# PixelWing_rev0_1.net
KiCad netlist of a schematic drawn in EAGLE
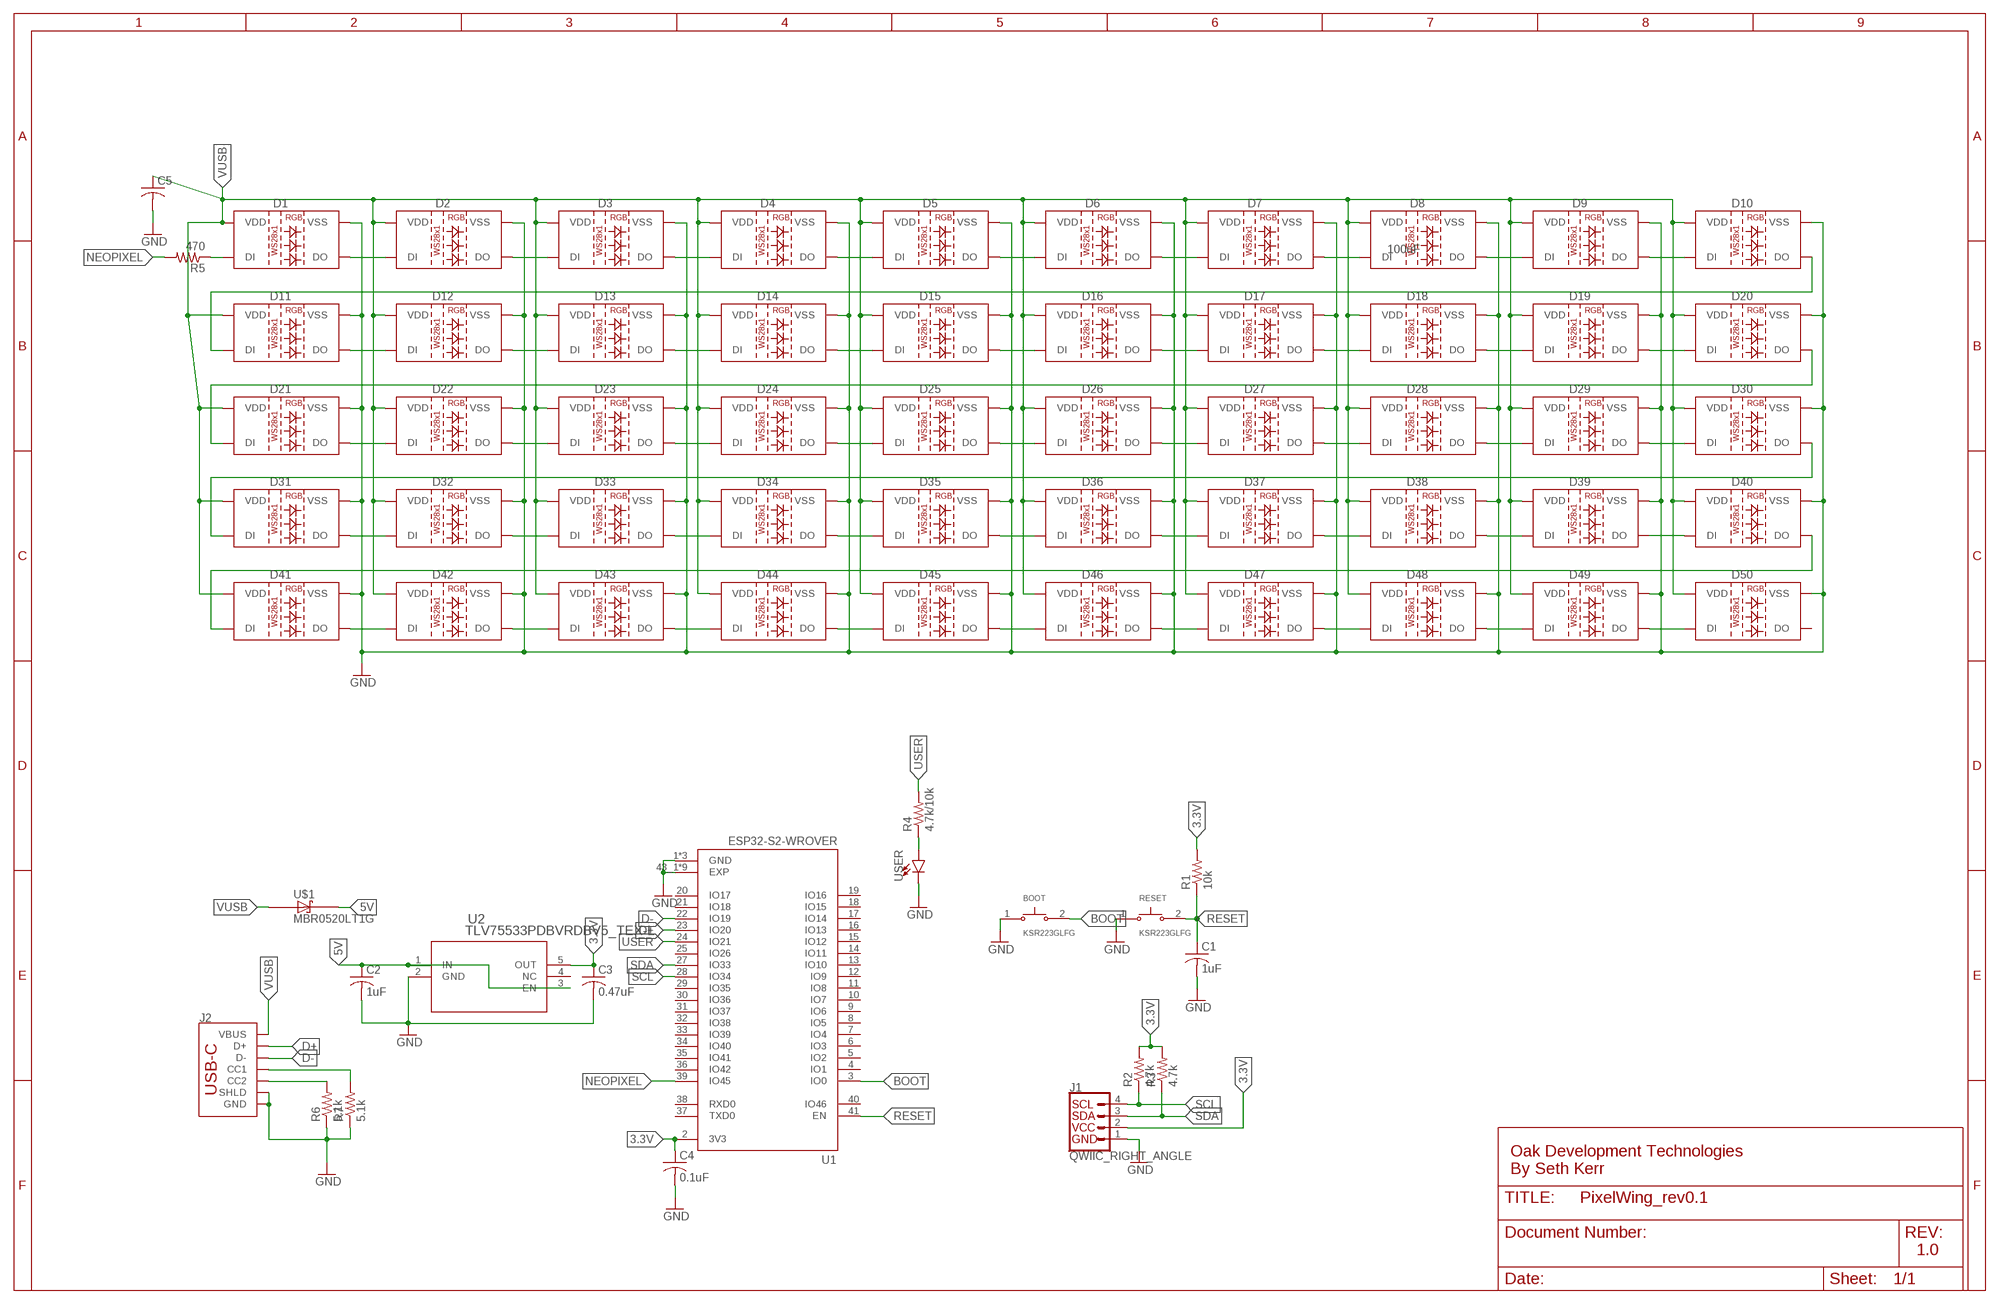
[diagram p0: schematic, sheet 1]

(export (version "E")
  (design (tool "Eeschema 10.0.6"))
  (components
    (comp (ref "BOOT")
      (value "KSR223GLFG")
      (footprint "eagle-import:SW_KSR223GLFG")
      (fields (field (name "MF") "C&K"))
      (libsource (lib "eagle-import") (part "KSR223GLFG"))
    )
    (comp (ref "C1")
      (value "1uF")
      (footprint "eagle-import:C0603")
      (libsource (lib "eagle-import") (part "C-USC0603"))
    )
    (comp (ref "C2")
      (value "1uF")
      (footprint "eagle-import:C0603")
      (libsource (lib "eagle-import") (part "C-USC0603"))
    )
    (comp (ref "C3")
      (value "0.47uF")
      (footprint "eagle-import:C0603")
      (libsource (lib "eagle-import") (part "C-USC0603"))
    )
    (comp (ref "C4")
      (value "0.1uF")
      (footprint "eagle-import:C0603")
      (libsource (lib "eagle-import") (part "C-USC0603"))
    )
    (comp (ref "C5")
      (value "100uF")
      (footprint "eagle-import:C1206")
      (libsource (lib "eagle-import") (part "C-USC1206"))
    )
    (comp (ref "D1")
      (value "WS2812BWS2812B-3535")
      (footprint "eagle-import:WS2812-3535")
      (libsource (lib "eagle-import") (part "WS2812BWS2812B-3535"))
    )
    (comp (ref "D2")
      (value "WS2812BWS2812B-3535")
      (footprint "eagle-import:WS2812-3535")
      (libsource (lib "eagle-import") (part "WS2812BWS2812B-3535"))
    )
    (comp (ref "D3")
      (value "WS2812BWS2812B-3535")
      (footprint "eagle-import:WS2812-3535")
      (libsource (lib "eagle-import") (part "WS2812BWS2812B-3535"))
    )
    (comp (ref "D4")
      (value "WS2812BWS2812B-3535")
      (footprint "eagle-import:WS2812-3535")
      (libsource (lib "eagle-import") (part "WS2812BWS2812B-3535"))
    )
    (comp (ref "D5")
      (value "WS2812BWS2812B-3535")
      (footprint "eagle-import:WS2812-3535")
      (libsource (lib "eagle-import") (part "WS2812BWS2812B-3535"))
    )
    (comp (ref "D6")
      (value "WS2812BWS2812B-3535")
      (footprint "eagle-import:WS2812-3535")
      (libsource (lib "eagle-import") (part "WS2812BWS2812B-3535"))
    )
    (comp (ref "D7")
      (value "WS2812BWS2812B-3535")
      (footprint "eagle-import:WS2812-3535")
      (libsource (lib "eagle-import") (part "WS2812BWS2812B-3535"))
    )
    (comp (ref "D8")
      (value "WS2812BWS2812B-3535")
      (footprint "eagle-import:WS2812-3535")
      (libsource (lib "eagle-import") (part "WS2812BWS2812B-3535"))
    )
    (comp (ref "D9")
      (value "WS2812BWS2812B-3535")
      (footprint "eagle-import:WS2812-3535")
      (libsource (lib "eagle-import") (part "WS2812BWS2812B-3535"))
    )
    (comp (ref "D10")
      (value "WS2812BWS2812B-3535")
      (footprint "eagle-import:WS2812-3535")
      (libsource (lib "eagle-import") (part "WS2812BWS2812B-3535"))
    )
    (comp (ref "D11")
      (value "WS2812BWS2812B-3535")
      (footprint "eagle-import:WS2812-3535")
      (libsource (lib "eagle-import") (part "WS2812BWS2812B-3535"))
    )
    (comp (ref "D12")
      (value "WS2812BWS2812B-3535")
      (footprint "eagle-import:WS2812-3535")
      (libsource (lib "eagle-import") (part "WS2812BWS2812B-3535"))
    )
    (comp (ref "D13")
      (value "WS2812BWS2812B-3535")
      (footprint "eagle-import:WS2812-3535")
      (libsource (lib "eagle-import") (part "WS2812BWS2812B-3535"))
    )
    (comp (ref "D14")
      (value "WS2812BWS2812B-3535")
      (footprint "eagle-import:WS2812-3535")
      (libsource (lib "eagle-import") (part "WS2812BWS2812B-3535"))
    )
    (comp (ref "D15")
      (value "WS2812BWS2812B-3535")
      (footprint "eagle-import:WS2812-3535")
      (libsource (lib "eagle-import") (part "WS2812BWS2812B-3535"))
    )
    (comp (ref "D16")
      (value "WS2812BWS2812B-3535")
      (footprint "eagle-import:WS2812-3535")
      (libsource (lib "eagle-import") (part "WS2812BWS2812B-3535"))
    )
    (comp (ref "D17")
      (value "WS2812BWS2812B-3535")
      (footprint "eagle-import:WS2812-3535")
      (libsource (lib "eagle-import") (part "WS2812BWS2812B-3535"))
    )
    (comp (ref "D18")
      (value "WS2812BWS2812B-3535")
      (footprint "eagle-import:WS2812-3535")
      (libsource (lib "eagle-import") (part "WS2812BWS2812B-3535"))
    )
    (comp (ref "D19")
      (value "WS2812BWS2812B-3535")
      (footprint "eagle-import:WS2812-3535")
      (libsource (lib "eagle-import") (part "WS2812BWS2812B-3535"))
    )
    (comp (ref "D20")
      (value "WS2812BWS2812B-3535")
      (footprint "eagle-import:WS2812-3535")
      (libsource (lib "eagle-import") (part "WS2812BWS2812B-3535"))
    )
    (comp (ref "D21")
      (value "WS2812BWS2812B-3535")
      (footprint "eagle-import:WS2812-3535")
      (libsource (lib "eagle-import") (part "WS2812BWS2812B-3535"))
    )
    (comp (ref "D22")
      (value "WS2812BWS2812B-3535")
      (footprint "eagle-import:WS2812-3535")
      (libsource (lib "eagle-import") (part "WS2812BWS2812B-3535"))
    )
    (comp (ref "D23")
      (value "WS2812BWS2812B-3535")
      (footprint "eagle-import:WS2812-3535")
      (libsource (lib "eagle-import") (part "WS2812BWS2812B-3535"))
    )
    (comp (ref "D24")
      (value "WS2812BWS2812B-3535")
      (footprint "eagle-import:WS2812-3535")
      (libsource (lib "eagle-import") (part "WS2812BWS2812B-3535"))
    )
    (comp (ref "D25")
      (value "WS2812BWS2812B-3535")
      (footprint "eagle-import:WS2812-3535")
      (libsource (lib "eagle-import") (part "WS2812BWS2812B-3535"))
    )
    (comp (ref "D26")
      (value "WS2812BWS2812B-3535")
      (footprint "eagle-import:WS2812-3535")
      (libsource (lib "eagle-import") (part "WS2812BWS2812B-3535"))
    )
    (comp (ref "D27")
      (value "WS2812BWS2812B-3535")
      (footprint "eagle-import:WS2812-3535")
      (libsource (lib "eagle-import") (part "WS2812BWS2812B-3535"))
    )
    (comp (ref "D28")
      (value "WS2812BWS2812B-3535")
      (footprint "eagle-import:WS2812-3535")
      (libsource (lib "eagle-import") (part "WS2812BWS2812B-3535"))
    )
    (comp (ref "D29")
      (value "WS2812BWS2812B-3535")
      (footprint "eagle-import:WS2812-3535")
      (libsource (lib "eagle-import") (part "WS2812BWS2812B-3535"))
    )
    (comp (ref "D30")
      (value "WS2812BWS2812B-3535")
      (footprint "eagle-import:WS2812-3535")
      (libsource (lib "eagle-import") (part "WS2812BWS2812B-3535"))
    )
    (comp (ref "D31")
      (value "WS2812BWS2812B-3535")
      (footprint "eagle-import:WS2812-3535")
      (libsource (lib "eagle-import") (part "WS2812BWS2812B-3535"))
    )
    (comp (ref "D32")
      (value "WS2812BWS2812B-3535")
      (footprint "eagle-import:WS2812-3535")
      (libsource (lib "eagle-import") (part "WS2812BWS2812B-3535"))
    )
    (comp (ref "D33")
      (value "WS2812BWS2812B-3535")
      (footprint "eagle-import:WS2812-3535")
      (libsource (lib "eagle-import") (part "WS2812BWS2812B-3535"))
    )
    (comp (ref "D34")
      (value "WS2812BWS2812B-3535")
      (footprint "eagle-import:WS2812-3535")
      (libsource (lib "eagle-import") (part "WS2812BWS2812B-3535"))
    )
    (comp (ref "D35")
      (value "WS2812BWS2812B-3535")
      (footprint "eagle-import:WS2812-3535")
      (libsource (lib "eagle-import") (part "WS2812BWS2812B-3535"))
    )
    (comp (ref "D36")
      (value "WS2812BWS2812B-3535")
      (footprint "eagle-import:WS2812-3535")
      (libsource (lib "eagle-import") (part "WS2812BWS2812B-3535"))
    )
    (comp (ref "D37")
      (value "WS2812BWS2812B-3535")
      (footprint "eagle-import:WS2812-3535")
      (libsource (lib "eagle-import") (part "WS2812BWS2812B-3535"))
    )
    (comp (ref "D38")
      (value "WS2812BWS2812B-3535")
      (footprint "eagle-import:WS2812-3535")
      (libsource (lib "eagle-import") (part "WS2812BWS2812B-3535"))
    )
    (comp (ref "D39")
      (value "WS2812BWS2812B-3535")
      (footprint "eagle-import:WS2812-3535")
      (libsource (lib "eagle-import") (part "WS2812BWS2812B-3535"))
    )
    (comp (ref "D40")
      (value "WS2812BWS2812B-3535")
      (footprint "eagle-import:WS2812-3535")
      (libsource (lib "eagle-import") (part "WS2812BWS2812B-3535"))
    )
    (comp (ref "D41")
      (value "WS2812BWS2812B-3535")
      (footprint "eagle-import:WS2812-3535")
      (libsource (lib "eagle-import") (part "WS2812BWS2812B-3535"))
    )
    (comp (ref "D42")
      (value "WS2812BWS2812B-3535")
      (footprint "eagle-import:WS2812-3535")
      (libsource (lib "eagle-import") (part "WS2812BWS2812B-3535"))
    )
    (comp (ref "D43")
      (value "WS2812BWS2812B-3535")
      (footprint "eagle-import:WS2812-3535")
      (libsource (lib "eagle-import") (part "WS2812BWS2812B-3535"))
    )
    (comp (ref "D44")
      (value "WS2812BWS2812B-3535")
      (footprint "eagle-import:WS2812-3535")
      (libsource (lib "eagle-import") (part "WS2812BWS2812B-3535"))
    )
    (comp (ref "D45")
      (value "WS2812BWS2812B-3535")
      (footprint "eagle-import:WS2812-3535")
      (libsource (lib "eagle-import") (part "WS2812BWS2812B-3535"))
    )
    (comp (ref "D46")
      (value "WS2812BWS2812B-3535")
      (footprint "eagle-import:WS2812-3535")
      (libsource (lib "eagle-import") (part "WS2812BWS2812B-3535"))
    )
    (comp (ref "D47")
      (value "WS2812BWS2812B-3535")
      (footprint "eagle-import:WS2812-3535")
      (libsource (lib "eagle-import") (part "WS2812BWS2812B-3535"))
    )
    (comp (ref "D48")
      (value "WS2812BWS2812B-3535")
      (footprint "eagle-import:WS2812-3535")
      (libsource (lib "eagle-import") (part "WS2812BWS2812B-3535"))
    )
    (comp (ref "D49")
      (value "WS2812BWS2812B-3535")
      (footprint "eagle-import:WS2812-3535")
      (libsource (lib "eagle-import") (part "WS2812BWS2812B-3535"))
    )
    (comp (ref "D50")
      (value "WS2812BWS2812B-3535")
      (footprint "eagle-import:WS2812-3535")
      (libsource (lib "eagle-import") (part "WS2812BWS2812B-3535"))
    )
    (comp (ref "J1")
      (value "QWIIC_RIGHT_ANGLE")
      (footprint "eagle-import:JST04_1MM_RA")
      (libsource (lib "eagle-import") (part "QWIIC_CONNECTORJS-1MM"))
    )
    (comp (ref "J2")
      (value "USB_C_2-LAYER_PADS")
      (footprint "eagle-import:USB-C-16P-2LAYER-PADS")
      (libsource (lib "eagle-import") (part "USB_C_2-LAYER_PADS"))
    )
    (comp (ref "R1")
      (value "10k")
      (footprint "eagle-import:R0603")
      (libsource (lib "eagle-import") (part "R-US_R0603"))
    )
    (comp (ref "R2")
      (value "4.7k")
      (footprint "eagle-import:R0603")
      (libsource (lib "eagle-import") (part "R-US_R0603"))
    )
    (comp (ref "R3")
      (value "4.7k")
      (footprint "eagle-import:R0603")
      (libsource (lib "eagle-import") (part "R-US_R0603"))
    )
    (comp (ref "R4")
      (value "4.7k/10k")
      (footprint "eagle-import:R0603")
      (libsource (lib "eagle-import") (part "R-US_R0603"))
    )
    (comp (ref "R5")
      (value "470")
      (footprint "eagle-import:R0603")
      (libsource (lib "eagle-import") (part "R-US_R0603"))
    )
    (comp (ref "R6")
      (value "5.1k")
      (footprint "eagle-import:R0603")
      (libsource (lib "eagle-import") (part "R-US_R0603"))
    )
    (comp (ref "R7")
      (value "5.1k")
      (footprint "eagle-import:R0603")
      (libsource (lib "eagle-import") (part "R-US_R0603"))
    )
    (comp (ref "RESET")
      (value "KSR223GLFG")
      (footprint "eagle-import:SW_KSR223GLFG")
      (fields (field (name "MF") "C&K"))
      (libsource (lib "eagle-import") (part "KSR223GLFG"))
    )
    (comp (ref "U$1")
      (value "MBR0520LT1G")
      (footprint "eagle-import:SOD3716X117(SOD-123)")
      (fields (field (name "MF") "ON Semiconductor"))
      (libsource (lib "eagle-import") (part "MBR0520LT1G"))
    )
    (comp (ref "U1")
      (value "ESP32-S2-WROVER")
      (footprint "eagle-import:MODULE_ESP32-S2-WROVER")
      (fields (field (name "MF") "Espressif Systems"))
      (libsource (lib "eagle-import") (part "ESP32-S2-WROVER"))
    )
    (comp (ref "U2")
      (value "TLV75533PDBVRDBV5_TEX-L")
      (footprint "eagle-import:DBV5_TEX-L")
      (fields
        (field (name "MANUFACTURER_PART_NUMBER") "TLV75533PDBVR")
        (field (name "COPYRIGHT") "Copyright (C) 2018 Accelerated Designs. All rights reserved")
      )
      (libsource (lib "eagle-import") (part "TLV75533PDBVRDBV5_TEX-L"))
    )
    (comp (ref "USER")
      (value "LED0603")
      (footprint "eagle-import:LED-0603")
      (libsource (lib "eagle-import") (part "LED0603"))
    )
  )
  (nets
    (net (code "1") (name "3.3V") (class "Default")
      (node (ref "C3") (pin "1") (pinfunction "1_1") (pintype "passive"))
      (node (ref "C4") (pin "1") (pinfunction "1_1") (pintype "passive"))
      (node (ref "J1") (pin "2") (pinfunction "2_2") (pintype "power_in"))
      (node (ref "R1") (pin "2") (pinfunction "2_2") (pintype "passive"))
      (node (ref "R2") (pin "2") (pinfunction "2_2") (pintype "passive"))
      (node (ref "R3") (pin "2") (pinfunction "2_2") (pintype "passive"))
      (node (ref "U1") (pin "2") (pinfunction "3V3_2") (pintype "power_in"))
      (node (ref "U2") (pin "5") (pinfunction "OUT_5") (pintype "output"))
    )
    (net (code "2") (name "5V") (class "Default")
      (node (ref "C2") (pin "1") (pinfunction "1_1") (pintype "passive"))
      (node (ref "U$1") (pin "1") (pinfunction "C_1") (pintype "passive"))
      (node (ref "U2") (pin "1") (pinfunction "IN_1") (pintype "input"))
      (node (ref "U2") (pin "3") (pinfunction "EN_3") (pintype "input"))
    )
    (net (code "3") (name "BOOT") (class "Default")
      (node (ref "BOOT") (pin "2") (pinfunction "2_2") (pintype "passive"))
      (node (ref "U1") (pin "3") (pinfunction "IO0_3") (pintype "bidirectional"))
    )
    (net (code "4") (name "D+") (class "Default")
      (node (ref "J2") (pin "A6") (pinfunction "D+_A6") (pintype "bidirectional"))
      (node (ref "J2") (pin "B6") (pinfunction "D+_B6") (pintype "bidirectional"))
      (node (ref "U1") (pin "23") (pinfunction "IO20_23") (pintype "bidirectional"))
    )
    (net (code "5") (name "D-") (class "Default")
      (node (ref "J2") (pin "A7") (pinfunction "D-_A7") (pintype "bidirectional"))
      (node (ref "J2") (pin "B7") (pinfunction "D-_B7") (pintype "bidirectional"))
      (node (ref "U1") (pin "22") (pinfunction "IO19_22") (pintype "bidirectional"))
    )
    (net (code "6") (name "GND") (class "Default")
      (node (ref "BOOT") (pin "1") (pinfunction "1_1") (pintype "passive"))
      (node (ref "C1") (pin "2") (pinfunction "2_2") (pintype "passive"))
      (node (ref "C2") (pin "2") (pinfunction "2_2") (pintype "passive"))
      (node (ref "C3") (pin "2") (pinfunction "2_2") (pintype "passive"))
      (node (ref "C4") (pin "2") (pinfunction "2_2") (pintype "passive"))
      (node (ref "C5") (pin "2") (pinfunction "2_2") (pintype "passive"))
      (node (ref "D1") (pin "VSS") (pinfunction "VSS_VSS") (pintype "bidirectional"))
      (node (ref "D10") (pin "VSS") (pinfunction "VSS_VSS") (pintype "bidirectional"))
      (node (ref "D11") (pin "VSS") (pinfunction "VSS_VSS") (pintype "bidirectional"))
      (node (ref "D12") (pin "VSS") (pinfunction "VSS_VSS") (pintype "bidirectional"))
      (node (ref "D13") (pin "VSS") (pinfunction "VSS_VSS") (pintype "bidirectional"))
      (node (ref "D14") (pin "VSS") (pinfunction "VSS_VSS") (pintype "bidirectional"))
      (node (ref "D15") (pin "VSS") (pinfunction "VSS_VSS") (pintype "bidirectional"))
      (node (ref "D16") (pin "VSS") (pinfunction "VSS_VSS") (pintype "bidirectional"))
      (node (ref "D17") (pin "VSS") (pinfunction "VSS_VSS") (pintype "bidirectional"))
      (node (ref "D18") (pin "VSS") (pinfunction "VSS_VSS") (pintype "bidirectional"))
      (node (ref "D19") (pin "VSS") (pinfunction "VSS_VSS") (pintype "bidirectional"))
      (node (ref "D2") (pin "VSS") (pinfunction "VSS_VSS") (pintype "bidirectional"))
      (node (ref "D20") (pin "VSS") (pinfunction "VSS_VSS") (pintype "bidirectional"))
      (node (ref "D21") (pin "VSS") (pinfunction "VSS_VSS") (pintype "bidirectional"))
      (node (ref "D22") (pin "VSS") (pinfunction "VSS_VSS") (pintype "bidirectional"))
      (node (ref "D23") (pin "VSS") (pinfunction "VSS_VSS") (pintype "bidirectional"))
      (node (ref "D24") (pin "VSS") (pinfunction "VSS_VSS") (pintype "bidirectional"))
      (node (ref "D25") (pin "VSS") (pinfunction "VSS_VSS") (pintype "bidirectional"))
      (node (ref "D26") (pin "VSS") (pinfunction "VSS_VSS") (pintype "bidirectional"))
      (node (ref "D27") (pin "VSS") (pinfunction "VSS_VSS") (pintype "bidirectional"))
      (node (ref "D28") (pin "VSS") (pinfunction "VSS_VSS") (pintype "bidirectional"))
      (node (ref "D29") (pin "VSS") (pinfunction "VSS_VSS") (pintype "bidirectional"))
      (node (ref "D3") (pin "VSS") (pinfunction "VSS_VSS") (pintype "bidirectional"))
      (node (ref "D30") (pin "VSS") (pinfunction "VSS_VSS") (pintype "bidirectional"))
      (node (ref "D31") (pin "VSS") (pinfunction "VSS_VSS") (pintype "bidirectional"))
      (node (ref "D32") (pin "VSS") (pinfunction "VSS_VSS") (pintype "bidirectional"))
      (node (ref "D33") (pin "VSS") (pinfunction "VSS_VSS") (pintype "bidirectional"))
      (node (ref "D34") (pin "VSS") (pinfunction "VSS_VSS") (pintype "bidirectional"))
      (node (ref "D35") (pin "VSS") (pinfunction "VSS_VSS") (pintype "bidirectional"))
      (node (ref "D36") (pin "VSS") (pinfunction "VSS_VSS") (pintype "bidirectional"))
      (node (ref "D37") (pin "VSS") (pinfunction "VSS_VSS") (pintype "bidirectional"))
      (node (ref "D38") (pin "VSS") (pinfunction "VSS_VSS") (pintype "bidirectional"))
      (node (ref "D39") (pin "VSS") (pinfunction "VSS_VSS") (pintype "bidirectional"))
      (node (ref "D4") (pin "VSS") (pinfunction "VSS_VSS") (pintype "bidirectional"))
      (node (ref "D40") (pin "VSS") (pinfunction "VSS_VSS") (pintype "bidirectional"))
      (node (ref "D41") (pin "VSS") (pinfunction "VSS_VSS") (pintype "bidirectional"))
      (node (ref "D42") (pin "VSS") (pinfunction "VSS_VSS") (pintype "bidirectional"))
      (node (ref "D43") (pin "VSS") (pinfunction "VSS_VSS") (pintype "bidirectional"))
      (node (ref "D44") (pin "VSS") (pinfunction "VSS_VSS") (pintype "bidirectional"))
      (node (ref "D45") (pin "VSS") (pinfunction "VSS_VSS") (pintype "bidirectional"))
      (node (ref "D46") (pin "VSS") (pinfunction "VSS_VSS") (pintype "bidirectional"))
      (node (ref "D47") (pin "VSS") (pinfunction "VSS_VSS") (pintype "bidirectional"))
      (node (ref "D48") (pin "VSS") (pinfunction "VSS_VSS") (pintype "bidirectional"))
      (node (ref "D49") (pin "VSS") (pinfunction "VSS_VSS") (pintype "bidirectional"))
      (node (ref "D5") (pin "VSS") (pinfunction "VSS_VSS") (pintype "bidirectional"))
      (node (ref "D50") (pin "VSS") (pinfunction "VSS_VSS") (pintype "bidirectional"))
      (node (ref "D6") (pin "VSS") (pinfunction "VSS_VSS") (pintype "bidirectional"))
      (node (ref "D7") (pin "VSS") (pinfunction "VSS_VSS") (pintype "bidirectional"))
      (node (ref "D8") (pin "VSS") (pinfunction "VSS_VSS") (pintype "bidirectional"))
      (node (ref "D9") (pin "VSS") (pinfunction "VSS_VSS") (pintype "bidirectional"))
      (node (ref "J1") (pin "1") (pinfunction "1_1") (pintype "power_in"))
      (node (ref "J2") (pin "GND") (pinfunction "GND_GND") (pintype "bidirectional"))
      (node (ref "J2") (pin "GND2") (pinfunction "GND_GND2") (pintype "bidirectional"))
      (node (ref "J2") (pin "P$1") (pinfunction "SHLD_P$1") (pintype "bidirectional"))
      (node (ref "J2") (pin "P$2") (pinfunction "SHLD_P$2") (pintype "bidirectional"))
      (node (ref "J2") (pin "P$3") (pinfunction "SHLD_P$3") (pintype "bidirectional"))
      (node (ref "J2") (pin "P$4") (pinfunction "SHLD_P$4") (pintype "bidirectional"))
      (node (ref "J2") (pin "SHLD1") (pinfunction "SHLD_SHLD1") (pintype "bidirectional"))
      (node (ref "J2") (pin "SHLD2") (pinfunction "SHLD_SHLD2") (pintype "bidirectional"))
      (node (ref "J2") (pin "SHLD3") (pinfunction "SHLD_SHLD3") (pintype "bidirectional"))
      (node (ref "J2") (pin "SHLD4") (pinfunction "SHLD_SHLD4") (pintype "bidirectional"))
      (node (ref "R6") (pin "1") (pinfunction "1_1") (pintype "passive"))
      (node (ref "R7") (pin "1") (pinfunction "1_1") (pintype "passive"))
      (node (ref "RESET") (pin "1") (pinfunction "1_1") (pintype "passive"))
      (node (ref "U1") (pin "1") (pinfunction "GND_1") (pintype "power_in"))
      (node (ref "U1") (pin "26") (pinfunction "GND_26") (pintype "power_in"))
      (node (ref "U1") (pin "42") (pinfunction "GND_42") (pintype "power_in"))
      (node (ref "U1") (pin "43_1") (pinfunction "EXP_43_1") (pintype "power_in"))
      (node (ref "U1") (pin "43_2") (pinfunction "EXP_43_2") (pintype "power_in"))
      (node (ref "U1") (pin "43_3") (pinfunction "EXP_43_3") (pintype "power_in"))
      (node (ref "U1") (pin "43_4") (pinfunction "EXP_43_4") (pintype "power_in"))
      (node (ref "U1") (pin "43_5") (pinfunction "EXP_43_5") (pintype "power_in"))
      (node (ref "U1") (pin "43_6") (pinfunction "EXP_43_6") (pintype "power_in"))
      (node (ref "U1") (pin "43_7") (pinfunction "EXP_43_7") (pintype "power_in"))
      (node (ref "U1") (pin "43_8") (pinfunction "EXP_43_8") (pintype "power_in"))
      (node (ref "U1") (pin "43_9") (pinfunction "EXP_43_9") (pintype "power_in"))
      (node (ref "U2") (pin "2") (pinfunction "GND_2") (pintype "power_in"))
      (node (ref "USER") (pin "C") (pinfunction "C_C") (pintype "passive"))
    )
    (net (code "7") (name "NEOPIXEL") (class "Default")
      (node (ref "R5") (pin "2") (pinfunction "2_2") (pintype "passive"))
      (node (ref "U1") (pin "39") (pinfunction "IO45_39") (pintype "bidirectional"))
    )
    (net (code "8") (name "Net-(D1-DI)") (class "Default")
      (node (ref "D1") (pin "DIN") (pinfunction "DI_DIN") (pintype "bidirectional"))
      (node (ref "R5") (pin "1") (pinfunction "1_1") (pintype "passive"))
    )
    (net (code "9") (name "Net-(D1-DO)") (class "Default")
      (node (ref "D1") (pin "DOUT") (pinfunction "DO_DOUT") (pintype "bidirectional"))
      (node (ref "D2") (pin "DIN") (pinfunction "DI_DIN") (pintype "bidirectional"))
    )
    (net (code "10") (name "Net-(D2-DO)") (class "Default")
      (node (ref "D2") (pin "DOUT") (pinfunction "DO_DOUT") (pintype "bidirectional"))
      (node (ref "D3") (pin "DIN") (pinfunction "DI_DIN") (pintype "bidirectional"))
    )
    (net (code "11") (name "Net-(D3-DO)") (class "Default")
      (node (ref "D3") (pin "DOUT") (pinfunction "DO_DOUT") (pintype "bidirectional"))
      (node (ref "D4") (pin "DIN") (pinfunction "DI_DIN") (pintype "bidirectional"))
    )
    (net (code "12") (name "Net-(D4-DO)") (class "Default")
      (node (ref "D4") (pin "DOUT") (pinfunction "DO_DOUT") (pintype "bidirectional"))
      (node (ref "D5") (pin "DIN") (pinfunction "DI_DIN") (pintype "bidirectional"))
    )
    (net (code "13") (name "Net-(D5-DO)") (class "Default")
      (node (ref "D5") (pin "DOUT") (pinfunction "DO_DOUT") (pintype "bidirectional"))
      (node (ref "D6") (pin "DIN") (pinfunction "DI_DIN") (pintype "bidirectional"))
    )
    (net (code "14") (name "Net-(D6-DO)") (class "Default")
      (node (ref "D6") (pin "DOUT") (pinfunction "DO_DOUT") (pintype "bidirectional"))
      (node (ref "D7") (pin "DIN") (pinfunction "DI_DIN") (pintype "bidirectional"))
    )
    (net (code "15") (name "Net-(D7-DO)") (class "Default")
      (node (ref "D7") (pin "DOUT") (pinfunction "DO_DOUT") (pintype "bidirectional"))
      (node (ref "D8") (pin "DIN") (pinfunction "DI_DIN") (pintype "bidirectional"))
    )
    (net (code "16") (name "Net-(D8-DO)") (class "Default")
      (node (ref "D8") (pin "DOUT") (pinfunction "DO_DOUT") (pintype "bidirectional"))
      (node (ref "D9") (pin "DIN") (pinfunction "DI_DIN") (pintype "bidirectional"))
    )
    (net (code "17") (name "Net-(D10-DI)") (class "Default")
      (node (ref "D10") (pin "DIN") (pinfunction "DI_DIN") (pintype "bidirectional"))
      (node (ref "D9") (pin "DOUT") (pinfunction "DO_DOUT") (pintype "bidirectional"))
    )
    (net (code "18") (name "Net-(D10-DO)") (class "Default")
      (node (ref "D10") (pin "DOUT") (pinfunction "DO_DOUT") (pintype "bidirectional"))
      (node (ref "D11") (pin "DIN") (pinfunction "DI_DIN") (pintype "bidirectional"))
    )
    (net (code "19") (name "Net-(D11-DO)") (class "Default")
      (node (ref "D11") (pin "DOUT") (pinfunction "DO_DOUT") (pintype "bidirectional"))
      (node (ref "D12") (pin "DIN") (pinfunction "DI_DIN") (pintype "bidirectional"))
    )
    (net (code "20") (name "Net-(D12-DO)") (class "Default")
      (node (ref "D12") (pin "DOUT") (pinfunction "DO_DOUT") (pintype "bidirectional"))
      (node (ref "D13") (pin "DIN") (pinfunction "DI_DIN") (pintype "bidirectional"))
    )
    (net (code "21") (name "Net-(D13-DO)") (class "Default")
      (node (ref "D13") (pin "DOUT") (pinfunction "DO_DOUT") (pintype "bidirectional"))
      (node (ref "D14") (pin "DIN") (pinfunction "DI_DIN") (pintype "bidirectional"))
    )
    (net (code "22") (name "Net-(D14-DO)") (class "Default")
      (node (ref "D14") (pin "DOUT") (pinfunction "DO_DOUT") (pintype "bidirectional"))
      (node (ref "D15") (pin "DIN") (pinfunction "DI_DIN") (pintype "bidirectional"))
    )
    (net (code "23") (name "Net-(D15-DO)") (class "Default")
      (node (ref "D15") (pin "DOUT") (pinfunction "DO_DOUT") (pintype "bidirectional"))
      (node (ref "D16") (pin "DIN") (pinfunction "DI_DIN") (pintype "bidirectional"))
    )
    (net (code "24") (name "Net-(D16-DO)") (class "Default")
      (node (ref "D16") (pin "DOUT") (pinfunction "DO_DOUT") (pintype "bidirectional"))
      (node (ref "D17") (pin "DIN") (pinfunction "DI_DIN") (pintype "bidirectional"))
    )
    (net (code "25") (name "Net-(D17-DO)") (class "Default")
      (node (ref "D17") (pin "DOUT") (pinfunction "DO_DOUT") (pintype "bidirectional"))
      (node (ref "D18") (pin "DIN") (pinfunction "DI_DIN") (pintype "bidirectional"))
    )
    (net (code "26") (name "Net-(D18-DO)") (class "Default")
      (node (ref "D18") (pin "DOUT") (pinfunction "DO_DOUT") (pintype "bidirectional"))
      (node (ref "D19") (pin "DIN") (pinfunction "DI_DIN") (pintype "bidirectional"))
    )
    (net (code "27") (name "Net-(D19-DO)") (class "Default")
      (node (ref "D19") (pin "DOUT") (pinfunction "DO_DOUT") (pintype "bidirectional"))
      (node (ref "D20") (pin "DIN") (pinfunction "DI_DIN") (pintype "bidirectional"))
    )
    (net (code "28") (name "Net-(D20-DO)") (class "Default")
      (node (ref "D20") (pin "DOUT") (pinfunction "DO_DOUT") (pintype "bidirectional"))
      (node (ref "D21") (pin "DIN") (pinfunction "DI_DIN") (pintype "bidirectional"))
    )
    (net (code "29") (name "Net-(D21-DO)") (class "Default")
      (node (ref "D21") (pin "DOUT") (pinfunction "DO_DOUT") (pintype "bidirectional"))
      (node (ref "D22") (pin "DIN") (pinfunction "DI_DIN") (pintype "bidirectional"))
    )
    (net (code "30") (name "Net-(D22-DO)") (class "Default")
      (node (ref "D22") (pin "DOUT") (pinfunction "DO_DOUT") (pintype "bidirectional"))
      (node (ref "D23") (pin "DIN") (pinfunction "DI_DIN") (pintype "bidirectional"))
    )
    (net (code "31") (name "Net-(D23-DO)") (class "Default")
      (node (ref "D23") (pin "DOUT") (pinfunction "DO_DOUT") (pintype "bidirectional"))
      (node (ref "D24") (pin "DIN") (pinfunction "DI_DIN") (pintype "bidirectional"))
    )
    (net (code "32") (name "Net-(D24-DO)") (class "Default")
      (node (ref "D24") (pin "DOUT") (pinfunction "DO_DOUT") (pintype "bidirectional"))
      (node (ref "D25") (pin "DIN") (pinfunction "DI_DIN") (pintype "bidirectional"))
    )
    (net (code "33") (name "Net-(D25-DO)") (class "Default")
      (node (ref "D25") (pin "DOUT") (pinfunction "DO_DOUT") (pintype "bidirectional"))
      (node (ref "D26") (pin "DIN") (pinfunction "DI_DIN") (pintype "bidirectional"))
    )
    (net (code "34") (name "Net-(D26-DO)") (class "Default")
      (node (ref "D26") (pin "DOUT") (pinfunction "DO_DOUT") (pintype "bidirectional"))
      (node (ref "D27") (pin "DIN") (pinfunction "DI_DIN") (pintype "bidirectional"))
    )
    (net (code "35") (name "Net-(D27-DO)") (class "Default")
      (node (ref "D27") (pin "DOUT") (pinfunction "DO_DOUT") (pintype "bidirectional"))
      (node (ref "D28") (pin "DIN") (pinfunction "DI_DIN") (pintype "bidirectional"))
    )
    (net (code "36") (name "Net-(D28-DO)") (class "Default")
      (node (ref "D28") (pin "DOUT") (pinfunction "DO_DOUT") (pintype "bidirectional"))
      (node (ref "D29") (pin "DIN") (pinfunction "DI_DIN") (pintype "bidirectional"))
    )
    (net (code "37") (name "Net-(D29-DO)") (class "Default")
      (node (ref "D29") (pin "DOUT") (pinfunction "DO_DOUT") (pintype "bidirectional"))
      (node (ref "D30") (pin "DIN") (pinfunction "DI_DIN") (pintype "bidirectional"))
    )
    (net (code "38") (name "Net-(D30-DO)") (class "Default")
      (node (ref "D30") (pin "DOUT") (pinfunction "DO_DOUT") (pintype "bidirectional"))
      (node (ref "D31") (pin "DIN") (pinfunction "DI_DIN") (pintype "bidirectional"))
    )
    (net (code "39") (name "Net-(D31-DO)") (class "Default")
      (node (ref "D31") (pin "DOUT") (pinfunction "DO_DOUT") (pintype "bidirectional"))
      (node (ref "D32") (pin "DIN") (pinfunction "DI_DIN") (pintype "bidirectional"))
    )
    (net (code "40") (name "Net-(D32-DO)") (class "Default")
      (node (ref "D32") (pin "DOUT") (pinfunction "DO_DOUT") (pintype "bidirectional"))
      (node (ref "D33") (pin "DIN") (pinfunction "DI_DIN") (pintype "bidirectional"))
    )
    (net (code "41") (name "Net-(D33-DO)") (class "Default")
      (node (ref "D33") (pin "DOUT") (pinfunction "DO_DOUT") (pintype "bidirectional"))
      (node (ref "D34") (pin "DIN") (pinfunction "DI_DIN") (pintype "bidirectional"))
    )
    (net (code "42") (name "Net-(D34-DO)") (class "Default")
      (node (ref "D34") (pin "DOUT") (pinfunction "DO_DOUT") (pintype "bidirectional"))
      (node (ref "D35") (pin "DIN") (pinfunction "DI_DIN") (pintype "bidirectional"))
    )
    (net (code "43") (name "Net-(D35-DO)") (class "Default")
      (node (ref "D35") (pin "DOUT") (pinfunction "DO_DOUT") (pintype "bidirectional"))
      (node (ref "D36") (pin "DIN") (pinfunction "DI_DIN") (pintype "bidirectional"))
    )
    (net (code "44") (name "Net-(D36-DO)") (class "Default")
      (node (ref "D36") (pin "DOUT") (pinfunction "DO_DOUT") (pintype "bidirectional"))
      (node (ref "D37") (pin "DIN") (pinfunction "DI_DIN") (pintype "bidirectional"))
    )
    (net (code "45") (name "Net-(D37-DO)") (class "Default")
      (node (ref "D37") (pin "DOUT") (pinfunction "DO_DOUT") (pintype "bidirectional"))
      (node (ref "D38") (pin "DIN") (pinfunction "DI_DIN") (pintype "bidirectional"))
    )
    (net (code "46") (name "Net-(D38-DO)") (class "Default")
      (node (ref "D38") (pin "DOUT") (pinfunction "DO_DOUT") (pintype "bidirectional"))
      (node (ref "D39") (pin "DIN") (pinfunction "DI_DIN") (pintype "bidirectional"))
    )
    (net (code "47") (name "Net-(D39-DO)") (class "Default")
      (node (ref "D39") (pin "DOUT") (pinfunction "DO_DOUT") (pintype "bidirectional"))
      (node (ref "D40") (pin "DIN") (pinfunction "DI_DIN") (pintype "bidirectional"))
    )
    (net (code "48") (name "Net-(D40-DO)") (class "Default")
      (node (ref "D40") (pin "DOUT") (pinfunction "DO_DOUT") (pintype "bidirectional"))
      (node (ref "D41") (pin "DIN") (pinfunction "DI_DIN") (pintype "bidirectional"))
    )
    (net (code "49") (name "Net-(D41-DO)") (class "Default")
      (node (ref "D41") (pin "DOUT") (pinfunction "DO_DOUT") (pintype "bidirectional"))
      (node (ref "D42") (pin "DIN") (pinfunction "DI_DIN") (pintype "bidirectional"))
    )
    (net (code "50") (name "Net-(D42-DO)") (class "Default")
      (node (ref "D42") (pin "DOUT") (pinfunction "DO_DOUT") (pintype "bidirectional"))
      (node (ref "D43") (pin "DIN") (pinfunction "DI_DIN") (pintype "bidirectional"))
    )
    (net (code "51") (name "Net-(D43-DO)") (class "Default")
      (node (ref "D43") (pin "DOUT") (pinfunction "DO_DOUT") (pintype "bidirectional"))
      (node (ref "D44") (pin "DIN") (pinfunction "DI_DIN") (pintype "bidirectional"))
    )
    (net (code "52") (name "Net-(D44-DO)") (class "Default")
      (node (ref "D44") (pin "DOUT") (pinfunction "DO_DOUT") (pintype "bidirectional"))
      (node (ref "D45") (pin "DIN") (pinfunction "DI_DIN") (pintype "bidirectional"))
    )
    (net (code "53") (name "Net-(D45-DO)") (class "Default")
      (node (ref "D45") (pin "DOUT") (pinfunction "DO_DOUT") (pintype "bidirectional"))
      (node (ref "D46") (pin "DIN") (pinfunction "DI_DIN") (pintype "bidirectional"))
    )
    (net (code "54") (name "Net-(D46-DO)") (class "Default")
      (node (ref "D46") (pin "DOUT") (pinfunction "DO_DOUT") (pintype "bidirectional"))
      (node (ref "D47") (pin "DIN") (pinfunction "DI_DIN") (pintype "bidirectional"))
    )
    (net (code "55") (name "Net-(D47-DO)") (class "Default")
      (node (ref "D47") (pin "DOUT") (pinfunction "DO_DOUT") (pintype "bidirectional"))
      (node (ref "D48") (pin "DIN") (pinfunction "DI_DIN") (pintype "bidirectional"))
    )
    (net (code "56") (name "Net-(D48-DO)") (class "Default")
      (node (ref "D48") (pin "DOUT") (pinfunction "DO_DOUT") (pintype "bidirectional"))
      (node (ref "D49") (pin "DIN") (pinfunction "DI_DIN") (pintype "bidirectional"))
    )
    (net (code "57") (name "Net-(D49-DO)") (class "Default")
      (node (ref "D49") (pin "DOUT") (pinfunction "DO_DOUT") (pintype "bidirectional"))
      (node (ref "D50") (pin "DIN") (pinfunction "DI_DIN") (pintype "bidirectional"))
    )
    (net (code "58") (name "Net-(J2-CC1)") (class "Default")
      (node (ref "J2") (pin "A5") (pinfunction "CC1_A5") (pintype "bidirectional"))
      (node (ref "R7") (pin "2") (pinfunction "2_2") (pintype "passive"))
    )
    (net (code "59") (name "Net-(J2-CC2)") (class "Default")
      (node (ref "J2") (pin "B5") (pinfunction "CC2_B5") (pintype "bidirectional"))
      (node (ref "R6") (pin "2") (pinfunction "2_2") (pintype "passive"))
    )
    (net (code "60") (name "Net-(R4-Pad1)") (class "Default")
      (node (ref "R4") (pin "1") (pinfunction "1_1") (pintype "passive"))
      (node (ref "USER") (pin "A") (pinfunction "A_A") (pintype "passive"))
    )
    (net (code "61") (name "RESET") (class "Default")
      (node (ref "C1") (pin "1") (pinfunction "1_1") (pintype "passive"))
      (node (ref "R1") (pin "1") (pinfunction "1_1") (pintype "passive"))
      (node (ref "RESET") (pin "2") (pinfunction "2_2") (pintype "passive"))
      (node (ref "U1") (pin "41") (pinfunction "EN_41") (pintype "input"))
    )
    (net (code "62") (name "SCL") (class "Default")
      (node (ref "J1") (pin "4") (pinfunction "4_4") (pintype "passive"))
      (node (ref "R2") (pin "1") (pinfunction "1_1") (pintype "passive"))
      (node (ref "U1") (pin "28") (pinfunction "IO34_28") (pintype "bidirectional"))
    )
    (net (code "63") (name "SDA") (class "Default")
      (node (ref "J1") (pin "3") (pinfunction "3_3") (pintype "passive"))
      (node (ref "R3") (pin "1") (pinfunction "1_1") (pintype "passive"))
      (node (ref "U1") (pin "27") (pinfunction "IO33_27") (pintype "bidirectional"))
    )
    (net (code "64") (name "USER") (class "Default")
      (node (ref "R4") (pin "2") (pinfunction "2_2") (pintype "passive"))
      (node (ref "U1") (pin "24") (pinfunction "IO21_24") (pintype "bidirectional"))
    )
    (net (code "65") (name "VUSB") (class "Default")
      (node (ref "C5") (pin "1") (pinfunction "1_1") (pintype "passive"))
      (node (ref "D1") (pin "VDD") (pinfunction "VDD_VDD") (pintype "bidirectional"))
      (node (ref "D10") (pin "VDD") (pinfunction "VDD_VDD") (pintype "bidirectional"))
      (node (ref "D11") (pin "VDD") (pinfunction "VDD_VDD") (pintype "bidirectional"))
      (node (ref "D12") (pin "VDD") (pinfunction "VDD_VDD") (pintype "bidirectional"))
      (node (ref "D13") (pin "VDD") (pinfunction "VDD_VDD") (pintype "bidirectional"))
      (node (ref "D14") (pin "VDD") (pinfunction "VDD_VDD") (pintype "bidirectional"))
      (node (ref "D15") (pin "VDD") (pinfunction "VDD_VDD") (pintype "bidirectional"))
      (node (ref "D16") (pin "VDD") (pinfunction "VDD_VDD") (pintype "bidirectional"))
      (node (ref "D17") (pin "VDD") (pinfunction "VDD_VDD") (pintype "bidirectional"))
      (node (ref "D18") (pin "VDD") (pinfunction "VDD_VDD") (pintype "bidirectional"))
      (node (ref "D19") (pin "VDD") (pinfunction "VDD_VDD") (pintype "bidirectional"))
      (node (ref "D2") (pin "VDD") (pinfunction "VDD_VDD") (pintype "bidirectional"))
      (node (ref "D20") (pin "VDD") (pinfunction "VDD_VDD") (pintype "bidirectional"))
      (node (ref "D21") (pin "VDD") (pinfunction "VDD_VDD") (pintype "bidirectional"))
      (node (ref "D22") (pin "VDD") (pinfunction "VDD_VDD") (pintype "bidirectional"))
      (node (ref "D23") (pin "VDD") (pinfunction "VDD_VDD") (pintype "bidirectional"))
      (node (ref "D24") (pin "VDD") (pinfunction "VDD_VDD") (pintype "bidirectional"))
      (node (ref "D25") (pin "VDD") (pinfunction "VDD_VDD") (pintype "bidirectional"))
      (node (ref "D26") (pin "VDD") (pinfunction "VDD_VDD") (pintype "bidirectional"))
      (node (ref "D27") (pin "VDD") (pinfunction "VDD_VDD") (pintype "bidirectional"))
      (node (ref "D28") (pin "VDD") (pinfunction "VDD_VDD") (pintype "bidirectional"))
      (node (ref "D29") (pin "VDD") (pinfunction "VDD_VDD") (pintype "bidirectional"))
      (node (ref "D3") (pin "VDD") (pinfunction "VDD_VDD") (pintype "bidirectional"))
      (node (ref "D30") (pin "VDD") (pinfunction "VDD_VDD") (pintype "bidirectional"))
      (node (ref "D31") (pin "VDD") (pinfunction "VDD_VDD") (pintype "bidirectional"))
      (node (ref "D32") (pin "VDD") (pinfunction "VDD_VDD") (pintype "bidirectional"))
      (node (ref "D33") (pin "VDD") (pinfunction "VDD_VDD") (pintype "bidirectional"))
      (node (ref "D34") (pin "VDD") (pinfunction "VDD_VDD") (pintype "bidirectional"))
      (node (ref "D35") (pin "VDD") (pinfunction "VDD_VDD") (pintype "bidirectional"))
      (node (ref "D36") (pin "VDD") (pinfunction "VDD_VDD") (pintype "bidirectional"))
      (node (ref "D37") (pin "VDD") (pinfunction "VDD_VDD") (pintype "bidirectional"))
      (node (ref "D38") (pin "VDD") (pinfunction "VDD_VDD") (pintype "bidirectional"))
      (node (ref "D39") (pin "VDD") (pinfunction "VDD_VDD") (pintype "bidirectional"))
      (node (ref "D4") (pin "VDD") (pinfunction "VDD_VDD") (pintype "bidirectional"))
      (node (ref "D40") (pin "VDD") (pinfunction "VDD_VDD") (pintype "bidirectional"))
      (node (ref "D41") (pin "VDD") (pinfunction "VDD_VDD") (pintype "bidirectional"))
      (node (ref "D42") (pin "VDD") (pinfunction "VDD_VDD") (pintype "bidirectional"))
      (node (ref "D43") (pin "VDD") (pinfunction "VDD_VDD") (pintype "bidirectional"))
      (node (ref "D44") (pin "VDD") (pinfunction "VDD_VDD") (pintype "bidirectional"))
      (node (ref "D45") (pin "VDD") (pinfunction "VDD_VDD") (pintype "bidirectional"))
      (node (ref "D46") (pin "VDD") (pinfunction "VDD_VDD") (pintype "bidirectional"))
      (node (ref "D47") (pin "VDD") (pinfunction "VDD_VDD") (pintype "bidirectional"))
      (node (ref "D48") (pin "VDD") (pinfunction "VDD_VDD") (pintype "bidirectional"))
      (node (ref "D49") (pin "VDD") (pinfunction "VDD_VDD") (pintype "bidirectional"))
      (node (ref "D5") (pin "VDD") (pinfunction "VDD_VDD") (pintype "bidirectional"))
      (node (ref "D50") (pin "VDD") (pinfunction "VDD_VDD") (pintype "bidirectional"))
      (node (ref "D6") (pin "VDD") (pinfunction "VDD_VDD") (pintype "bidirectional"))
      (node (ref "D7") (pin "VDD") (pinfunction "VDD_VDD") (pintype "bidirectional"))
      (node (ref "D8") (pin "VDD") (pinfunction "VDD_VDD") (pintype "bidirectional"))
      (node (ref "D9") (pin "VDD") (pinfunction "VDD_VDD") (pintype "bidirectional"))
      (node (ref "J2") (pin "VBUS1") (pinfunction "VBUS_VBUS1") (pintype "bidirectional"))
      (node (ref "J2") (pin "VBUS2") (pinfunction "VBUS_VBUS2") (pintype "bidirectional"))
      (node (ref "U$1") (pin "2") (pinfunction "A_2") (pintype "passive"))
    )
    (net (code "66") (name "unconnected-(D50-DO-PadDOUT)") (class "Default")
      (node (ref "D50") (pin "DOUT") (pinfunction "DO_DOUT") (pintype "bidirectional"))
    )
    (net (code "67") (name "unconnected-(U1-IO1-Pad4)") (class "Default")
      (node (ref "U1") (pin "4") (pinfunction "IO1_4") (pintype "bidirectional"))
    )
    (net (code "68") (name "unconnected-(U1-IO2-Pad5)") (class "Default")
      (node (ref "U1") (pin "5") (pinfunction "IO2_5") (pintype "bidirectional"))
    )
    (net (code "69") (name "unconnected-(U1-IO3-Pad6)") (class "Default")
      (node (ref "U1") (pin "6") (pinfunction "IO3_6") (pintype "bidirectional"))
    )
    (net (code "70") (name "unconnected-(U1-IO4-Pad7)") (class "Default")
      (node (ref "U1") (pin "7") (pinfunction "IO4_7") (pintype "bidirectional"))
    )
    (net (code "71") (name "unconnected-(U1-IO5-Pad8)") (class "Default")
      (node (ref "U1") (pin "8") (pinfunction "IO5_8") (pintype "bidirectional"))
    )
    (net (code "72") (name "unconnected-(U1-IO6-Pad9)") (class "Default")
      (node (ref "U1") (pin "9") (pinfunction "IO6_9") (pintype "bidirectional"))
    )
    (net (code "73") (name "unconnected-(U1-IO7-Pad10)") (class "Default")
      (node (ref "U1") (pin "10") (pinfunction "IO7_10") (pintype "bidirectional"))
    )
    (net (code "74") (name "unconnected-(U1-IO8-Pad11)") (class "Default")
      (node (ref "U1") (pin "11") (pinfunction "IO8_11") (pintype "bidirectional"))
    )
    (net (code "75") (name "unconnected-(U1-IO9-Pad12)") (class "Default")
      (node (ref "U1") (pin "12") (pinfunction "IO9_12") (pintype "bidirectional"))
    )
    (net (code "76") (name "unconnected-(U1-IO10-Pad13)") (class "Default")
      (node (ref "U1") (pin "13") (pinfunction "IO10_13") (pintype "bidirectional"))
    )
    (net (code "77") (name "unconnected-(U1-IO11-Pad14)") (class "Default")
      (node (ref "U1") (pin "14") (pinfunction "IO11_14") (pintype "bidirectional"))
    )
    (net (code "78") (name "unconnected-(U1-IO12-Pad15)") (class "Default")
      (node (ref "U1") (pin "15") (pinfunction "IO12_15") (pintype "bidirectional"))
    )
    (net (code "79") (name "unconnected-(U1-IO13-Pad16)") (class "Default")
      (node (ref "U1") (pin "16") (pinfunction "IO13_16") (pintype "bidirectional"))
    )
    (net (code "80") (name "unconnected-(U1-IO14-Pad17)") (class "Default")
      (node (ref "U1") (pin "17") (pinfunction "IO14_17") (pintype "bidirectional"))
    )
    (net (code "81") (name "unconnected-(U1-IO15-Pad18)") (class "Default")
      (node (ref "U1") (pin "18") (pinfunction "IO15_18") (pintype "bidirectional"))
    )
    (net (code "82") (name "unconnected-(U1-IO16-Pad19)") (class "Default")
      (node (ref "U1") (pin "19") (pinfunction "IO16_19") (pintype "bidirectional"))
    )
    (net (code "83") (name "unconnected-(U1-IO17-Pad20)") (class "Default")
      (node (ref "U1") (pin "20") (pinfunction "IO17_20") (pintype "bidirectional"))
    )
    (net (code "84") (name "unconnected-(U1-IO18-Pad21)") (class "Default")
      (node (ref "U1") (pin "21") (pinfunction "IO18_21") (pintype "bidirectional"))
    )
    (net (code "85") (name "unconnected-(U1-IO26-Pad25)") (class "Default")
      (node (ref "U1") (pin "25") (pinfunction "IO26_25") (pintype "bidirectional"))
    )
    (net (code "86") (name "unconnected-(U1-IO35-Pad29)") (class "Default")
      (node (ref "U1") (pin "29") (pinfunction "IO35_29") (pintype "bidirectional"))
    )
    (net (code "87") (name "unconnected-(U1-IO36-Pad30)") (class "Default")
      (node (ref "U1") (pin "30") (pinfunction "IO36_30") (pintype "bidirectional"))
    )
    (net (code "88") (name "unconnected-(U1-IO37-Pad31)") (class "Default")
      (node (ref "U1") (pin "31") (pinfunction "IO37_31") (pintype "bidirectional"))
    )
    (net (code "89") (name "unconnected-(U1-IO38-Pad32)") (class "Default")
      (node (ref "U1") (pin "32") (pinfunction "IO38_32") (pintype "bidirectional"))
    )
    (net (code "90") (name "unconnected-(U1-IO39-Pad33)") (class "Default")
      (node (ref "U1") (pin "33") (pinfunction "IO39_33") (pintype "bidirectional"))
    )
    (net (code "91") (name "unconnected-(U1-IO40-Pad34)") (class "Default")
      (node (ref "U1") (pin "34") (pinfunction "IO40_34") (pintype "bidirectional"))
    )
    (net (code "92") (name "unconnected-(U1-IO41-Pad35)") (class "Default")
      (node (ref "U1") (pin "35") (pinfunction "IO41_35") (pintype "bidirectional"))
    )
    (net (code "93") (name "unconnected-(U1-IO42-Pad36)") (class "Default")
      (node (ref "U1") (pin "36") (pinfunction "IO42_36") (pintype "bidirectional"))
    )
    (net (code "94") (name "unconnected-(U1-IO46-Pad40)") (class "Default")
      (node (ref "U1") (pin "40") (pinfunction "IO46_40") (pintype "input"))
    )
    (net (code "95") (name "unconnected-(U1-RXD0-Pad38)") (class "Default")
      (node (ref "U1") (pin "38") (pinfunction "RXD0_38") (pintype "bidirectional"))
    )
    (net (code "96") (name "unconnected-(U1-TXD0-Pad37)") (class "Default")
      (node (ref "U1") (pin "37") (pinfunction "TXD0_37") (pintype "bidirectional"))
    )
    (net (code "97") (name "unconnected-(U2-NC-Pad4)") (class "Default")
      (node (ref "U2") (pin "4") (pinfunction "NC_4") (pintype "no_connect"))
    )
  )
)
